# MAX232.net
KiCad netlist of a schematic drawn in Altium Designer
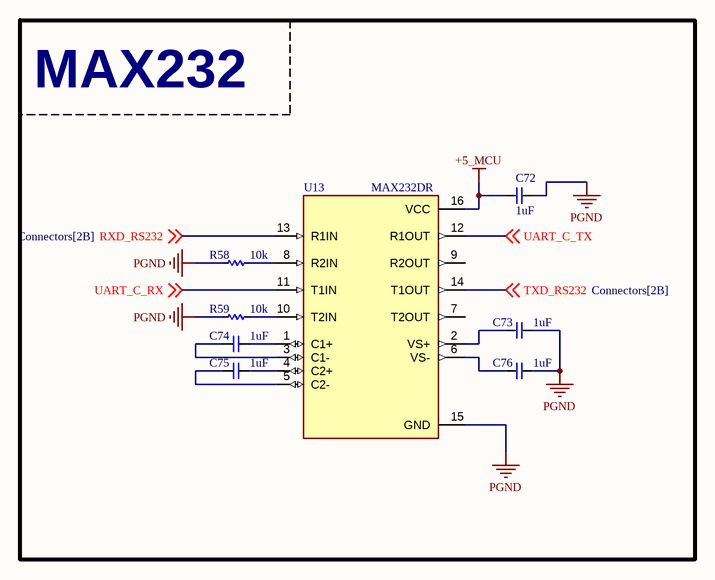
[diagram p0: MAX232.SchDoc]

(export (version "E")
  (design (tool "Eeschema 10.0.6"))
  (components
    (comp (ref "C72")
      (value "1uF")
      (footprint "CAP_C_1608X80")
      (description "CAP")
      (libsource (lib "LABLIB") (part "_CAP_C_2"))
    )
    (comp (ref "C73")
      (value "1uF")
      (footprint "CAP_C_1608X80")
      (description "CAP")
      (libsource (lib "LABLIB") (part "_CAP_C_2"))
    )
    (comp (ref "C74")
      (value "1uF")
      (footprint "CAP_C_1608X80")
      (description "CAP")
      (libsource (lib "LABLIB") (part "_CAP_C_2"))
    )
    (comp (ref "C75")
      (value "1uF")
      (footprint "CAP_C_1608X80")
      (description "CAP")
      (libsource (lib "LABLIB") (part "_CAP_C_2"))
    )
    (comp (ref "C76")
      (value "1uF")
      (footprint "CAP_C_1608X80")
      (description "CAP")
      (libsource (lib "LABLIB") (part "_CAP_C_2"))
    )
    (comp (ref "R58")
      (value "10k")
      (footprint "RES_C_1608X60")
      (description "RES")
      (libsource (lib "LABLIB") (part "_RES_B_2_2"))
    )
    (comp (ref "R59")
      (value "10k")
      (footprint "RES_C_1608X60")
      (description "RES")
      (libsource (lib "LABLIB") (part "_RES_B_2_2"))
    )
    (comp (ref "U13") (value "MAX232DR") (footprint "SOIC-16") (libsource (lib "new1") (part "MAX232DR")))
  )
  (nets
    (net (code "1") (name "+5_MCU") (class "Default")
      (node (ref "C72") (pin "2") (pinfunction "2_2") (pintype "passive"))
      (node (ref "U13") (pin "16") (pinfunction "VCC_16") (pintype "power_in"))
    )
    (net (code "2") (name "Net-(U13-C1+)") (class "Default")
      (node (ref "C74") (pin "1") (pinfunction "1_1") (pintype "passive"))
      (node (ref "U13") (pin "1") (pinfunction "C1+_1") (pintype "bidirectional"))
    )
    (net (code "3") (name "Net-(U13-C1-)") (class "Default")
      (node (ref "C74") (pin "2") (pinfunction "2_2") (pintype "passive"))
      (node (ref "U13") (pin "3") (pinfunction "C1-_3") (pintype "bidirectional"))
    )
    (net (code "4") (name "Net-(U13-C2+)") (class "Default")
      (node (ref "C75") (pin "1") (pinfunction "1_1") (pintype "passive"))
      (node (ref "U13") (pin "4") (pinfunction "C2+_4") (pintype "bidirectional"))
    )
    (net (code "5") (name "Net-(U13-C2-)") (class "Default")
      (node (ref "C75") (pin "2") (pinfunction "2_2") (pintype "passive"))
      (node (ref "U13") (pin "5") (pinfunction "C2-_5") (pintype "bidirectional"))
    )
    (net (code "6") (name "Net-(U13-R2IN)") (class "Default")
      (node (ref "R58") (pin "2") (pinfunction "2_2") (pintype "passive"))
      (node (ref "U13") (pin "8") (pinfunction "R2IN_8") (pintype "input"))
    )
    (net (code "7") (name "Net-(U13-T2IN)") (class "Default")
      (node (ref "R59") (pin "2") (pinfunction "2_2") (pintype "passive"))
      (node (ref "U13") (pin "10") (pinfunction "T2IN_10") (pintype "input"))
    )
    (net (code "8") (name "Net-(U13-VS+)") (class "Default")
      (node (ref "C73") (pin "2") (pinfunction "2_2") (pintype "passive"))
      (node (ref "U13") (pin "2") (pinfunction "VS+_2") (pintype "output"))
    )
    (net (code "9") (name "Net-(U13-VS-)") (class "Default")
      (node (ref "C76") (pin "2") (pinfunction "2_2") (pintype "passive"))
      (node (ref "U13") (pin "6") (pinfunction "VS-_6") (pintype "output"))
    )
    (net (code "10") (name "PGND") (class "Default")
      (node (ref "C72") (pin "1") (pinfunction "1_1") (pintype "passive"))
      (node (ref "C73") (pin "1") (pinfunction "1_1") (pintype "passive"))
      (node (ref "C76") (pin "1") (pinfunction "1_1") (pintype "passive"))
      (node (ref "R58") (pin "1") (pinfunction "1_1") (pintype "passive"))
      (node (ref "R59") (pin "1") (pinfunction "1_1") (pintype "passive"))
      (node (ref "U13") (pin "15") (pinfunction "GND_15") (pintype "power_in"))
    )
    (net (code "11") (name "RXD_RS232") (class "Default")
      (node (ref "U13") (pin "13") (pinfunction "R1IN_13") (pintype "input"))
    )
    (net (code "12") (name "TXD_RS232") (class "Default")
      (node (ref "U13") (pin "14") (pinfunction "T1OUT_14") (pintype "output"))
    )
    (net (code "13") (name "UART_C_RX") (class "Default")
      (node (ref "U13") (pin "11") (pinfunction "T1IN_11") (pintype "input"))
    )
    (net (code "14") (name "UART_C_TX") (class "Default")
      (node (ref "U13") (pin "12") (pinfunction "R1OUT_12") (pintype "output"))
    )
    (net (code "15") (name "unconnected-(U13-R2OUT-Pad9)") (class "Default")
      (node (ref "U13") (pin "9") (pinfunction "R2OUT_9") (pintype "output"))
    )
    (net (code "16") (name "unconnected-(U13-T2OUT-Pad7)") (class "Default")
      (node (ref "U13") (pin "7") (pinfunction "T2OUT_7") (pintype "output"))
    )
  )
)
